# BMS_Fan_Bat_Relay.net
KiCad netlist of a schematic drawn in Altium Designer
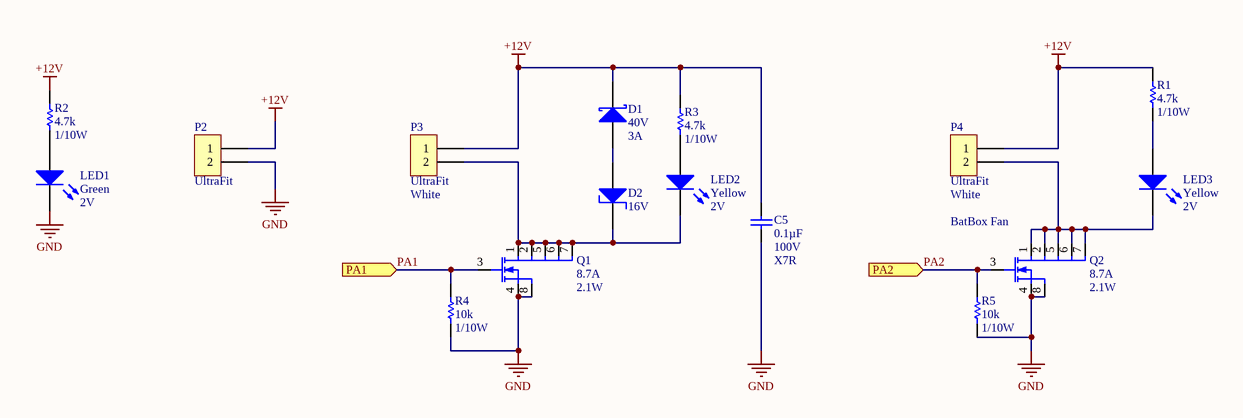
[diagram p0: BMS_Fan&Bat_Relay.SchDoc]

(export (version "E")
  (design (tool "Eeschema 10.0.6"))
  (components
    (comp (ref "C5")
      (value "CAP CER 0.1UF 100V 10% X7R 0805")
      (footprint "CAP, 0805")
      (description "0.1µF ±10% 100V Ceramic Capacitor X7R 0805 (2012 Metric)")
      (fields
        (field (name "TOLERANCE") "±10%")
        (field (name "CAPACITANCE") "0.1µF")
        (field (name "VOLTAGE") "100V")
        (field (name "TEMPERATURE COEFFICIENT") "X7R")
      )
      (libsource (lib "Schematic Diagrams") (part "CAP CER 0.1UF 100V 10% X7R 0805"))
    )
    (comp (ref "D1")
      (value "DIODE SCHOTTKY 40V 3A DO-214AA (SMB)")
      (footprint "DO-214AA Diode")
      (description "Diode Schottky 40V 3A Surface Mount DO-214AA (SMB)")
      (fields
        (field (name "VOLTAGE - DC REVERSE (VR) (MAX)") "40V")
        (field (name "CURRENT - AVERAGE RECTIFIED (IO)") "3A")
      )
      (libsource (lib "Schematic Diagrams") (part "DIODE SCHOTTKY 40V 3A DO-214AA (SMB)"))
    )
    (comp (ref "D2")
      (value "DIODE ZENER 16V 5W DO-214AA (SMB)")
      (footprint "DO-214AA Diode")
      (description "Zener Diode 16V 5W ±5% Surface Mount DO-214AA (SMB)")
      (fields
        (field (name "MANUFACTURE PART NUMBER") "SMBJ5353B-TP")
        (field (name "VOLTAGE - ZENER (NOM)") "16V")
      )
      (libsource (lib "Schematic Diagrams") (part "DIODE ZENER 16V 5W DO-214AA (SMB)"))
    )
    (comp (ref "LED1")
      (value "LED GREEN CLEAR 2V 0603")
      (footprint "LED_0603")
      (description "Green 572nm LED Indication - Discrete 2V 0603 (1608 Metric)")
      (fields
        (field (name "MANUFACTURER") "Wurth Electronics Inc.")
        (field (name "MANUFACTURER PART NUMBER") "150060VS75000")
        (field (name "COLOR") "Green")
        (field (name "VOLTAGE - FORWARD (VF) (TYP)") "2V")
      )
      (libsource (lib "Schematic Diagrams") (part "LED GREEN CLEAR 2V 0603"))
    )
    (comp (ref "LED2")
      (value "LED YELLOW CLEAR 2.1V 0603")
      (footprint "LED_0603")
      (description "Yellow 590nm LED Indication - Discrete 2V 0603 (1608 Metric)")
      (fields
        (field (name "MANUFACTURER") "Wurth Electronics Inc.")
        (field (name "MANUFACTURER PART NUMBER") "150060YS75000")
        (field (name "COLOR") "Yellow")
        (field (name "VOLTAGE - FORWARD (VF) (TYP)") "2V")
      )
      (libsource (lib "Schematic Diagrams") (part "LED YELLOW CLEAR 2.1V 0603"))
    )
    (comp (ref "LED3")
      (value "LED YELLOW CLEAR 2.1V 0603")
      (footprint "LED_0603")
      (description "Yellow 590nm LED Indication - Discrete 2V 0603 (1608 Metric)")
      (fields
        (field (name "MANUFACTURER") "Wurth Electronics Inc.")
        (field (name "MANUFACTURER PART NUMBER") "150060YS75000")
        (field (name "COLOR") "Yellow")
        (field (name "VOLTAGE - FORWARD (VF) (TYP)") "2V")
      )
      (libsource (lib "Schematic Diagrams") (part "LED YELLOW CLEAR 2.1V 0603"))
    )
    (comp (ref "P2")
      (value "CONN 2POS ULTRA-FIT 0.138\"")
      (footprint "CONN, 2POS ULTRA-FIT")
      (description "2 Positions Header, Shrouded Connector 0.138\" (3.50mm) Through Hole Gold")
      (fields (field (name "VOLTAGE") "400V") (field (name "SERIES") "UltraFit"))
      (libsource (lib "Schematic Diagrams") (part "CONN 2POS ULTRA-FIT 0.138{dblquote}"))
    )
    (comp (ref "P3")
      (value "CONN 2POS ULTRA-FIT NATURAL COLOR 0.138\"")
      (footprint "CONN, 2POS ULTRA-FIT - NATURAL COLOR")
      (description "2 Positions Header, Shrouded Connector 0.138\" (3.50mm) Through Hole")
      (fields
        (field (name "VOLTAGE") "400V")
        (field (name "SERIES") "UltraFit")
        (field (name "COLOR") "White")
      )
      (libsource (lib "Schematic Diagrams") (part "CONN 2POS ULTRA-FIT NATURAL COLOR 0.138{dblquote}"))
    )
    (comp (ref "P4")
      (value "CONN 2POS ULTRA-FIT NATURAL COLOR 0.138\"")
      (footprint "CONN, 2POS ULTRA-FIT - NATURAL COLOR")
      (description "2 Positions Header, Shrouded Connector 0.138\" (3.50mm) Through Hole")
      (fields
        (field (name "VOLTAGE") "400V")
        (field (name "SERIES") "UltraFit")
        (field (name "COLOR") "White")
      )
      (libsource (lib "Schematic Diagrams") (part "CONN 2POS ULTRA-FIT NATURAL COLOR 0.138{dblquote}"))
    )
    (comp (ref "Q1")
      (value "MOSFET N-CH 30V 8.7A 2.1W 6-PQFN (2x2)")
      (footprint "MOSFET N-CH 30V 12A 2mmx2mm PQFN")
      (fields
        (field (name "CURRENT - CONTINUOUS DRAIN (ID) @ 25°C") "8.7A")
        (field (name "POWER DISSIPATION (MAX)") "2.1W")
      )
      (libsource (lib "Schematic Diagrams") (part "MOSFET N-CH 30V 8.7A 2.1W 6-PQFN (2x2)"))
    )
    (comp (ref "Q2")
      (value "MOSFET N-CH 30V 8.7A 2.1W 6-PQFN (2x2)")
      (footprint "MOSFET N-CH 30V 12A 2mmx2mm PQFN")
      (fields
        (field (name "CURRENT - CONTINUOUS DRAIN (ID) @ 25°C") "8.7A")
        (field (name "POWER DISSIPATION (MAX)") "2.1W")
      )
      (libsource (lib "Schematic Diagrams") (part "MOSFET N-CH 30V 8.7A 2.1W 6-PQFN (2x2)"))
    )
    (comp (ref "R1")
      (value "RES 4.7K OHM 1% 1/10W 0603")
      (footprint "RES, 0603")
      (description "4.7k Ohm ±1% 0.1W, 1/10W Chip Resistor 0603 (1608 Metric) Moisture Resistant Thick Film")
      (fields
        (field (name "TOLERANCE") "±1%")
        (field (name "RESISTANCE (OHMS)") "4.7k")
        (field (name "POWER (WATTS)") "1/10W")
      )
      (libsource (lib "Schematic Diagrams") (part "RES 4.7K OHM 1% 1/10W 0603"))
    )
    (comp (ref "R2")
      (value "RES 4.7K OHM 1% 1/10W 0603")
      (footprint "RES, 0603")
      (description "4.7k Ohm ±1% 0.1W, 1/10W Chip Resistor 0603 (1608 Metric) Moisture Resistant Thick Film")
      (fields
        (field (name "TOLERANCE") "±1%")
        (field (name "RESISTANCE (OHMS)") "4.7k")
        (field (name "POWER (WATTS)") "1/10W")
      )
      (libsource (lib "Schematic Diagrams") (part "RES 4.7K OHM 1% 1/10W 0603"))
    )
    (comp (ref "R3")
      (value "RES 4.7K OHM 1% 1/10W 0603")
      (footprint "RES, 0603")
      (description "4.7k Ohm ±1% 0.1W, 1/10W Chip Resistor 0603 (1608 Metric) Moisture Resistant Thick Film")
      (fields
        (field (name "TOLERANCE") "±1%")
        (field (name "RESISTANCE (OHMS)") "4.7k")
        (field (name "POWER (WATTS)") "1/10W")
      )
      (libsource (lib "Schematic Diagrams") (part "RES 4.7K OHM 1% 1/10W 0603"))
    )
    (comp (ref "R4")
      (value "RES 10K OHM 1% 1/10W 0603")
      (footprint "RES, 0603")
      (description "RES SMD 10K OHM 1% 1/10W 0603")
      (fields
        (field (name "TOLERANCE") "±1%")
        (field (name "RESISTANCE") "10k")
        (field (name "POWER") "1/10W")
      )
      (libsource (lib "Schematic Diagrams") (part "RES 10K OHM 1% 1/10W 0603"))
    )
    (comp (ref "R5")
      (value "RES 10K OHM 1% 1/10W 0603")
      (footprint "RES, 0603")
      (description "RES SMD 10K OHM 1% 1/10W 0603")
      (fields
        (field (name "TOLERANCE") "±1%")
        (field (name "RESISTANCE") "10k")
        (field (name "POWER") "1/10W")
      )
      (libsource (lib "Schematic Diagrams") (part "RES 10K OHM 1% 1/10W 0603"))
    )
  )
  (nets
    (net (code "1") (name "+12V") (class "Default")
      (node (ref "C5") (pin "1") (pinfunction "1_1") (pintype "passive"))
      (node (ref "D1") (pin "2") (pinfunction "K_2") (pintype "passive"))
      (node (ref "P2") (pin "1") (pinfunction "1_1") (pintype "passive"))
      (node (ref "P3") (pin "1") (pinfunction "1_1") (pintype "passive"))
      (node (ref "P4") (pin "1") (pinfunction "1_1") (pintype "passive"))
      (node (ref "R1") (pin "1") (pinfunction "1_1") (pintype "passive"))
      (node (ref "R2") (pin "1") (pinfunction "1_1") (pintype "passive"))
      (node (ref "R3") (pin "1") (pinfunction "1_1") (pintype "passive"))
    )
    (net (code "2") (name "/PA1") (class "Default")
      (node (ref "Q1") (pin "3") (pinfunction "G_3") (pintype "passive"))
      (node (ref "R4") (pin "1") (pinfunction "1_1") (pintype "passive"))
    )
    (net (code "3") (name "/PA2") (class "Default")
      (node (ref "Q2") (pin "3") (pinfunction "G_3") (pintype "passive"))
      (node (ref "R5") (pin "1") (pinfunction "1_1") (pintype "passive"))
    )
    (net (code "4") (name "GND") (class "Default")
      (node (ref "C5") (pin "2") (pinfunction "2_2") (pintype "passive"))
      (node (ref "LED1") (pin "2") (pinfunction "K_2") (pintype "passive"))
      (node (ref "P2") (pin "2") (pinfunction "2_2") (pintype "passive"))
      (node (ref "Q1") (pin "4") (pinfunction "S_4") (pintype "passive"))
      (node (ref "Q1") (pin "8") (pinfunction "S_8") (pintype "passive"))
      (node (ref "Q2") (pin "4") (pinfunction "S_4") (pintype "passive"))
      (node (ref "Q2") (pin "8") (pinfunction "S_8") (pintype "passive"))
      (node (ref "R4") (pin "2") (pinfunction "2_2") (pintype "passive"))
      (node (ref "R5") (pin "2") (pinfunction "2_2") (pintype "passive"))
    )
    (net (code "5") (name "Net-(D1-A)") (class "Default")
      (node (ref "D1") (pin "1") (pinfunction "A_1") (pintype "passive"))
      (node (ref "D2") (pin "1") (pinfunction "A_1") (pintype "passive"))
    )
    (net (code "6") (name "Net-(D2-K)") (class "Default")
      (node (ref "D2") (pin "2") (pinfunction "K_2") (pintype "passive"))
      (node (ref "LED2") (pin "2") (pinfunction "K_2") (pintype "passive"))
      (node (ref "P3") (pin "2") (pinfunction "2_2") (pintype "passive"))
      (node (ref "Q1") (pin "1") (pinfunction "D_1") (pintype "passive"))
      (node (ref "Q1") (pin "2") (pinfunction "D_2") (pintype "passive"))
      (node (ref "Q1") (pin "5") (pinfunction "D_5") (pintype "passive"))
      (node (ref "Q1") (pin "6") (pinfunction "D_6") (pintype "passive"))
      (node (ref "Q1") (pin "7") (pinfunction "D_7") (pintype "passive"))
    )
    (net (code "7") (name "Net-(LED1-A)") (class "Default")
      (node (ref "LED1") (pin "1") (pinfunction "A_1") (pintype "passive"))
      (node (ref "R2") (pin "2") (pinfunction "2_2") (pintype "passive"))
    )
    (net (code "8") (name "Net-(LED2-A)") (class "Default")
      (node (ref "LED2") (pin "1") (pinfunction "A_1") (pintype "passive"))
      (node (ref "R3") (pin "2") (pinfunction "2_2") (pintype "passive"))
    )
    (net (code "9") (name "Net-(LED3-A)") (class "Default")
      (node (ref "LED3") (pin "1") (pinfunction "A_1") (pintype "passive"))
      (node (ref "R1") (pin "2") (pinfunction "2_2") (pintype "passive"))
    )
    (net (code "10") (name "Net-(LED3-K)") (class "Default")
      (node (ref "LED3") (pin "2") (pinfunction "K_2") (pintype "passive"))
      (node (ref "P4") (pin "2") (pinfunction "2_2") (pintype "passive"))
      (node (ref "Q2") (pin "1") (pinfunction "D_1") (pintype "passive"))
      (node (ref "Q2") (pin "2") (pinfunction "D_2") (pintype "passive"))
      (node (ref "Q2") (pin "5") (pinfunction "D_5") (pintype "passive"))
      (node (ref "Q2") (pin "6") (pinfunction "D_6") (pintype "passive"))
      (node (ref "Q2") (pin "7") (pinfunction "D_7") (pintype "passive"))
    )
  )
)
